# backplane_main.net
KiCad netlist of a schematic drawn in Altium Designer
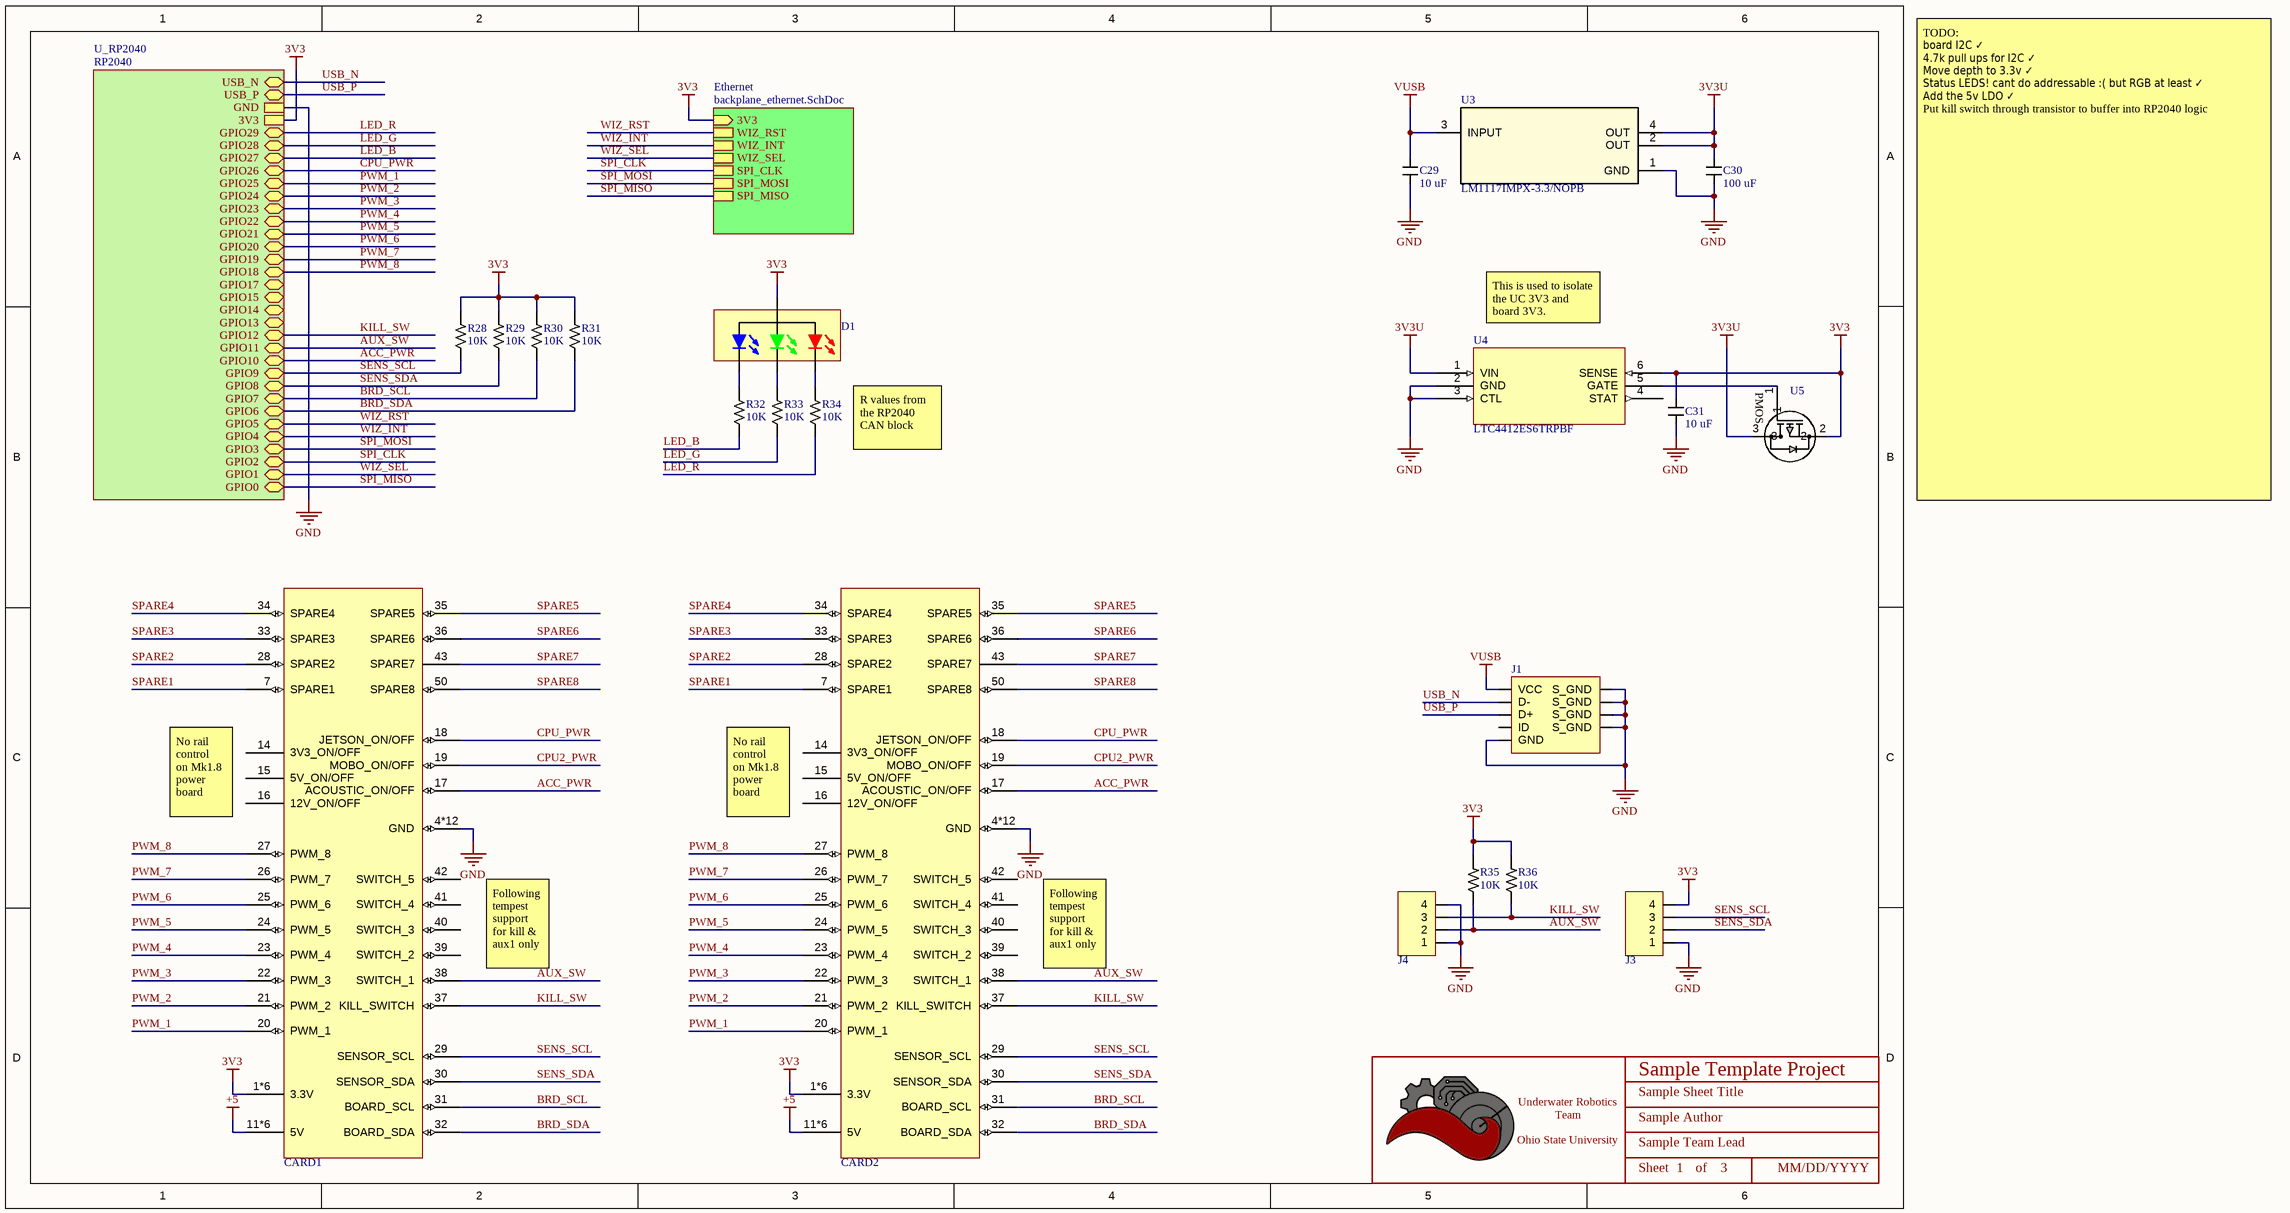
[diagram p0: backplane_main.SchDoc]

(export (version "E")
  (design (tool "Eeschema 10.0.6"))
  (components
    (comp (ref "*")
      (value "Title_Block")
      (footprint "LOGO")
      (description "UWRT Schematic Title Block Template\r\n\r\nCreated June 2021, Dylan Trainor")
      (libsource (lib "UWRT") (part "Title_Block"))
    )
    (comp (ref "C29")
      (value "10uF Ceramic 6.3V")
      (footprint "CAPACITOR_0603")
      (description "Cap 10uF 6.3V +/-20%\r\nCeramic 0603")
      (fields
        (field (name "TOLERANCE") "+/- 20%")
        (field (name "VOLTAGE") "6.3V")
        (field (name "VALUE (UF)") "10 uF")
        (field (name "MADE BY") "Flip B")
      )
      (libsource (lib "Capacitors") (part "CAPACITOR_10uF_0603"))
    )
    (comp (ref "C30")
      (value "100uF Ceramic 6.3V")
      (footprint "CAPACITOR_0603")
      (description "Cap 100uF 6.3V +/-20%\r\nCeramic 0603")
      (fields
        (field (name "TOLERANCE") "+/- 20%")
        (field (name "VOLTAGE") "6.3V")
        (field (name "VALUE (UF)") "100 uF")
        (field (name "MADE BY") "Dylan Trainor")
      )
      (libsource (lib "Capacitors") (part "CAPACITOR_100uF_0603"))
    )
    (comp (ref "C31")
      (value "10uF Ceramic 6.3V")
      (footprint "CAPACITOR_0603")
      (description "Cap 10uF 6.3V +/-20%\r\nCeramic 0603")
      (fields
        (field (name "TOLERANCE") "+/- 20%")
        (field (name "VOLTAGE") "6.3V")
        (field (name "VALUE (UF)") "10 uF")
        (field (name "MADE BY") "Flip B")
      )
      (libsource (lib "Capacitors") (part "CAPACITOR_10uF_0603"))
    )
    (comp (ref "CARD1")
      (value "BACKPLANE_EDGE_SOCKET")
      (footprint "SOCKET_BACKPLANE_EDGE_CONN")
      (description "Backplane Edge Socket")
      (fields (field (name "MADE BY") "Robert Pafford"))
      (libsource (lib "Connectors") (part "BACKPLANE_EDGE_SOCKET"))
    )
    (comp (ref "CARD2")
      (value "BACKPLANE_EDGE_SOCKET")
      (footprint "SOCKET_BACKPLANE_EDGE_CONN")
      (description "Backplane Edge Socket")
      (fields (field (name "MADE BY") "Robert Pafford"))
      (libsource (lib "Connectors") (part "BACKPLANE_EDGE_SOCKET"))
    )
    (comp (ref "D1")
      (value "EAST1616RGBB4")
      (footprint "LED_0606_4SMD")
      (description "LED RGB CLEAR 4SMD")
      (fields (field (name "MADE BY") "Robert Pafford"))
      (libsource (lib "Diodes") (part "LED_RGB_4SMD"))
    )
    (comp (ref "J1")
      (value "USB_MICRO R/A")
      (footprint "CONN_MINIUSB")
      (description "Amphenol Micro USB-B\r\nUSB2.0 5 Pin Right Angle SMD")
      (fields (field (name "MANUFACTURER") "Amphenol") (field (name "CREATED BY") "Flip B"))
      (libsource (lib "Connectors") (part "CONN_MICROUSB"))
    )
    (comp (ref "J3")
      (value "Mini-Fit Jr R/A")
      (footprint "CONN_MOLEX_MINIFIT JR_4 POS_R/A")
      (description "Molex Minifit Jr. 5569 \r\n4 Pos R/A Natural")
      (fields (field (name "MANUFACTURER") "Molex") (field (name "CREATED BY") "Flip B"))
      (libsource (lib "Connectors") (part "CONN_MOLEX_MINIFIT JR_4POS_R/A"))
    )
    (comp (ref "J4")
      (value "Mini-Fit Jr R/A")
      (footprint "CONN_MOLEX_MINIFIT JR_4 POS_R/A")
      (description "Molex Minifit Jr. 5569 \r\n4 Pos R/A Natural")
      (fields (field (name "MANUFACTURER") "Molex") (field (name "CREATED BY") "Flip B"))
      (libsource (lib "Connectors") (part "CONN_MOLEX_MINIFIT JR_4POS_R/A"))
    )
    (comp (ref "R28")
      (value "10k Ohm 5% 1/10W")
      (footprint "RESISTOR_0603")
      (description "RES 10k OHM 5% 1/10W 0603")
      (fields
        (field (name "TOLERANCE") "+/- 5%")
        (field (name "VALUE  (OHMS)") "10K")
        (field (name "MADE BY") "Robert Pafford")
      )
      (libsource (lib "Resistors") (part "RESISTOR_10K_0603"))
    )
    (comp (ref "R29")
      (value "10k Ohm 5% 1/10W")
      (footprint "RESISTOR_0603")
      (description "RES 10k OHM 5% 1/10W 0603")
      (fields
        (field (name "TOLERANCE") "+/- 5%")
        (field (name "VALUE  (OHMS)") "10K")
        (field (name "MADE BY") "Robert Pafford")
      )
      (libsource (lib "Resistors") (part "RESISTOR_10K_0603"))
    )
    (comp (ref "R30")
      (value "10k Ohm 5% 1/10W")
      (footprint "RESISTOR_0603")
      (description "RES 10k OHM 5% 1/10W 0603")
      (fields
        (field (name "TOLERANCE") "+/- 5%")
        (field (name "VALUE  (OHMS)") "10K")
        (field (name "MADE BY") "Robert Pafford")
      )
      (libsource (lib "Resistors") (part "RESISTOR_10K_0603"))
    )
    (comp (ref "R31")
      (value "10k Ohm 5% 1/10W")
      (footprint "RESISTOR_0603")
      (description "RES 10k OHM 5% 1/10W 0603")
      (fields
        (field (name "TOLERANCE") "+/- 5%")
        (field (name "VALUE  (OHMS)") "10K")
        (field (name "MADE BY") "Robert Pafford")
      )
      (libsource (lib "Resistors") (part "RESISTOR_10K_0603"))
    )
    (comp (ref "R32")
      (value "10k Ohm 5% 1/10W")
      (footprint "RESISTOR_0603")
      (description "RES 10k OHM 5% 1/10W 0603")
      (fields
        (field (name "TOLERANCE") "+/- 5%")
        (field (name "VALUE  (OHMS)") "10K")
        (field (name "MADE BY") "Robert Pafford")
      )
      (libsource (lib "Resistors") (part "RESISTOR_10K_0603"))
    )
    (comp (ref "R33")
      (value "10k Ohm 5% 1/10W")
      (footprint "RESISTOR_0603")
      (description "RES 10k OHM 5% 1/10W 0603")
      (fields
        (field (name "TOLERANCE") "+/- 5%")
        (field (name "VALUE  (OHMS)") "10K")
        (field (name "MADE BY") "Robert Pafford")
      )
      (libsource (lib "Resistors") (part "RESISTOR_10K_0603"))
    )
    (comp (ref "R34")
      (value "10k Ohm 5% 1/10W")
      (footprint "RESISTOR_0603")
      (description "RES 10k OHM 5% 1/10W 0603")
      (fields
        (field (name "TOLERANCE") "+/- 5%")
        (field (name "VALUE  (OHMS)") "10K")
        (field (name "MADE BY") "Robert Pafford")
      )
      (libsource (lib "Resistors") (part "RESISTOR_10K_0603"))
    )
    (comp (ref "R35")
      (value "10k Ohm 5% 1/10W")
      (footprint "RESISTOR_0603")
      (description "RES 10k OHM 5% 1/10W 0603")
      (fields
        (field (name "TOLERANCE") "+/- 5%")
        (field (name "VALUE  (OHMS)") "10K")
        (field (name "MADE BY") "Robert Pafford")
      )
      (libsource (lib "Resistors") (part "RESISTOR_10K_0603"))
    )
    (comp (ref "R36")
      (value "10k Ohm 5% 1/10W")
      (footprint "RESISTOR_0603")
      (description "RES 10k OHM 5% 1/10W 0603")
      (fields
        (field (name "TOLERANCE") "+/- 5%")
        (field (name "VALUE  (OHMS)") "10K")
        (field (name "MADE BY") "Robert Pafford")
      )
      (libsource (lib "Resistors") (part "RESISTOR_10K_0603"))
    )
    (comp (ref "U3")
      (value "LM1117IMPX-3.3/NOPB")
      (footprint "SOT-223-4")
      (description "IC REG LIN 3.3V 800MA SOT223-4")
      (fields
        (field (name "PARTNUMBER") "LM1117IMP-3.3/NOPB")
        (field (name "MANUFACTURER") "Texas Instruments")
        (field (name "CREATED BY") "Dylan T")
      )
      (libsource (lib "Converter") (part "LM1117IMPX-3.3/NOPB"))
    )
    (comp (ref "U4")
      (value "LTC4412ES6TRPBF")
      (footprint "TSOT-23_S6")
      (description "OR Controller Source Selector Switch P-Channel 2:1 TSOT-23-6")
      (fields (field (name "MP") "LTC4412ES6#TRPBF") (field (name "MF") "Analog Devices"))
      (libsource (lib "Integrated Circuits") (part "LTC4412ES6TRPBF"))
    )
    (comp (ref "U5")
      (value "MOSFET P-CHANNEL 20V 4.7A SOT23")
      (footprint "SOT-23-3")
      (description "P-Channel 20 V 4.7A (Tc) 1.56W (Tc) Surface Mount SOT-23")
      (fields
        (field (name "MANUFACTURER_PART_NUMBER") "TSM500P02CX")
        (field (name "CREATED BY") "Robert Pafford")
      )
      (libsource (lib "Transistors") (part "TSM500P02CX"))
    )
  )
  (nets
    (net (code "1") (name "+5") (class "Default")
      (node (ref "CARD1") (pin "11*6") (pinfunction "5V_11*6") (pintype "power_in"))
      (node (ref "CARD2") (pin "11*6") (pinfunction "5V_11*6") (pintype "power_in"))
    )
    (net (code "2") (name "/ACC_PWR") (class "Default")
      (node (ref "CARD1") (pin "17") (pinfunction "ACOUSTIC_ON/OFF_17") (pintype "bidirectional"))
      (node (ref "CARD2") (pin "17") (pinfunction "ACOUSTIC_ON/OFF_17") (pintype "bidirectional"))
    )
    (net (code "3") (name "/AUX_SW") (class "Default")
      (node (ref "CARD1") (pin "38") (pinfunction "SWITCH_1_38") (pintype "bidirectional"))
      (node (ref "CARD2") (pin "38") (pinfunction "SWITCH_1_38") (pintype "bidirectional"))
      (node (ref "J4") (pin "2") (pinfunction "2_2") (pintype "passive"))
      (node (ref "R35") (pin "2") (pinfunction "2_2") (pintype "passive"))
    )
    (net (code "4") (name "/BRD_SCL") (class "Default")
      (node (ref "CARD1") (pin "31") (pinfunction "BOARD_SCL_31") (pintype "bidirectional"))
      (node (ref "CARD2") (pin "31") (pinfunction "BOARD_SCL_31") (pintype "bidirectional"))
      (node (ref "R30") (pin "2") (pinfunction "2_2") (pintype "passive"))
    )
    (net (code "5") (name "/BRD_SDA") (class "Default")
      (node (ref "CARD1") (pin "32") (pinfunction "BOARD_SDA_32") (pintype "bidirectional"))
      (node (ref "CARD2") (pin "32") (pinfunction "BOARD_SDA_32") (pintype "bidirectional"))
      (node (ref "R31") (pin "2") (pinfunction "2_2") (pintype "passive"))
    )
    (net (code "6") (name "/CPU2_PWR") (class "Default")
      (node (ref "CARD1") (pin "19") (pinfunction "MOBO_ON/OFF_19") (pintype "bidirectional"))
      (node (ref "CARD2") (pin "19") (pinfunction "MOBO_ON/OFF_19") (pintype "bidirectional"))
    )
    (net (code "7") (name "/CPU_PWR") (class "Default")
      (node (ref "CARD1") (pin "18") (pinfunction "JETSON_ON/OFF_18") (pintype "bidirectional"))
      (node (ref "CARD2") (pin "18") (pinfunction "JETSON_ON/OFF_18") (pintype "bidirectional"))
    )
    (net (code "12") (name "/KILL_SW") (class "Default")
      (node (ref "CARD1") (pin "37") (pinfunction "KILL_SWITCH_37") (pintype "bidirectional"))
      (node (ref "CARD2") (pin "37") (pinfunction "KILL_SWITCH_37") (pintype "bidirectional"))
      (node (ref "J4") (pin "3") (pinfunction "3_3") (pintype "passive"))
      (node (ref "R36") (pin "2") (pinfunction "2_2") (pintype "passive"))
    )
    (net (code "13") (name "/LED_B") (class "Default")
      (node (ref "R32") (pin "2") (pinfunction "2_2") (pintype "passive"))
    )
    (net (code "14") (name "/LED_G") (class "Default")
      (node (ref "R33") (pin "2") (pinfunction "2_2") (pintype "passive"))
    )
    (net (code "15") (name "/LED_R") (class "Default")
      (node (ref "R34") (pin "2") (pinfunction "2_2") (pintype "passive"))
    )
    (net (code "16") (name "/PWM_1") (class "Default")
      (node (ref "CARD1") (pin "20") (pinfunction "PWM_1_20") (pintype "bidirectional"))
      (node (ref "CARD2") (pin "20") (pinfunction "PWM_1_20") (pintype "bidirectional"))
    )
    (net (code "17") (name "/PWM_2") (class "Default")
      (node (ref "CARD1") (pin "21") (pinfunction "PWM_2_21") (pintype "bidirectional"))
      (node (ref "CARD2") (pin "21") (pinfunction "PWM_2_21") (pintype "bidirectional"))
    )
    (net (code "18") (name "/PWM_3") (class "Default")
      (node (ref "CARD1") (pin "22") (pinfunction "PWM_3_22") (pintype "bidirectional"))
      (node (ref "CARD2") (pin "22") (pinfunction "PWM_3_22") (pintype "bidirectional"))
    )
    (net (code "19") (name "/PWM_4") (class "Default")
      (node (ref "CARD1") (pin "23") (pinfunction "PWM_4_23") (pintype "bidirectional"))
      (node (ref "CARD2") (pin "23") (pinfunction "PWM_4_23") (pintype "bidirectional"))
    )
    (net (code "20") (name "/PWM_5") (class "Default")
      (node (ref "CARD1") (pin "24") (pinfunction "PWM_5_24") (pintype "bidirectional"))
      (node (ref "CARD2") (pin "24") (pinfunction "PWM_5_24") (pintype "bidirectional"))
    )
    (net (code "21") (name "/PWM_6") (class "Default")
      (node (ref "CARD1") (pin "25") (pinfunction "PWM_6_25") (pintype "bidirectional"))
      (node (ref "CARD2") (pin "25") (pinfunction "PWM_6_25") (pintype "bidirectional"))
    )
    (net (code "22") (name "/PWM_7") (class "Default")
      (node (ref "CARD1") (pin "26") (pinfunction "PWM_7_26") (pintype "bidirectional"))
      (node (ref "CARD2") (pin "26") (pinfunction "PWM_7_26") (pintype "bidirectional"))
    )
    (net (code "23") (name "/PWM_8") (class "Default")
      (node (ref "CARD1") (pin "27") (pinfunction "PWM_8_27") (pintype "bidirectional"))
      (node (ref "CARD2") (pin "27") (pinfunction "PWM_8_27") (pintype "bidirectional"))
    )
    (net (code "24") (name "/SENS_SCL") (class "Default")
      (node (ref "CARD1") (pin "29") (pinfunction "SENSOR_SCL_29") (pintype "bidirectional"))
      (node (ref "CARD2") (pin "29") (pinfunction "SENSOR_SCL_29") (pintype "bidirectional"))
      (node (ref "J3") (pin "3") (pinfunction "3_3") (pintype "passive"))
      (node (ref "R28") (pin "2") (pinfunction "2_2") (pintype "passive"))
    )
    (net (code "25") (name "/SENS_SDA") (class "Default")
      (node (ref "CARD1") (pin "30") (pinfunction "SENSOR_SDA_30") (pintype "bidirectional"))
      (node (ref "CARD2") (pin "30") (pinfunction "SENSOR_SDA_30") (pintype "bidirectional"))
      (node (ref "J3") (pin "2") (pinfunction "2_2") (pintype "passive"))
      (node (ref "R29") (pin "2") (pinfunction "2_2") (pintype "passive"))
    )
    (net (code "26") (name "/SPARE1") (class "Default")
      (node (ref "CARD1") (pin "7") (pinfunction "SPARE1_7") (pintype "bidirectional"))
      (node (ref "CARD2") (pin "7") (pinfunction "SPARE1_7") (pintype "bidirectional"))
    )
    (net (code "27") (name "/SPARE2") (class "Default")
      (node (ref "CARD1") (pin "28") (pinfunction "SPARE2_28") (pintype "bidirectional"))
      (node (ref "CARD2") (pin "28") (pinfunction "SPARE2_28") (pintype "bidirectional"))
    )
    (net (code "28") (name "/SPARE3") (class "Default")
      (node (ref "CARD1") (pin "33") (pinfunction "SPARE3_33") (pintype "bidirectional"))
      (node (ref "CARD2") (pin "33") (pinfunction "SPARE3_33") (pintype "bidirectional"))
    )
    (net (code "29") (name "/SPARE4") (class "Default")
      (node (ref "CARD1") (pin "34") (pinfunction "SPARE4_34") (pintype "bidirectional"))
      (node (ref "CARD2") (pin "34") (pinfunction "SPARE4_34") (pintype "bidirectional"))
    )
    (net (code "30") (name "/SPARE5") (class "Default")
      (node (ref "CARD1") (pin "35") (pinfunction "SPARE5_35") (pintype "bidirectional"))
      (node (ref "CARD2") (pin "35") (pinfunction "SPARE5_35") (pintype "bidirectional"))
    )
    (net (code "31") (name "/SPARE6") (class "Default")
      (node (ref "CARD1") (pin "36") (pinfunction "SPARE6_36") (pintype "bidirectional"))
      (node (ref "CARD2") (pin "36") (pinfunction "SPARE6_36") (pintype "bidirectional"))
    )
    (net (code "32") (name "/SPARE7") (class "Default")
      (node (ref "CARD1") (pin "43") (pinfunction "SPARE7_43") (pintype "power_in"))
      (node (ref "CARD2") (pin "43") (pinfunction "SPARE7_43") (pintype "power_in"))
    )
    (net (code "33") (name "/SPARE8") (class "Default")
      (node (ref "CARD1") (pin "50") (pinfunction "SPARE8_50") (pintype "bidirectional"))
      (node (ref "CARD2") (pin "50") (pinfunction "SPARE8_50") (pintype "bidirectional"))
    )
    (net (code "37") (name "/USB_N") (class "Default")
      (node (ref "J1") (pin "2") (pinfunction "D-_2") (pintype "passive"))
    )
    (net (code "38") (name "/USB_P") (class "Default")
      (node (ref "J1") (pin "3") (pinfunction "D+_3") (pintype "passive"))
    )
    (net (code "42") (name "3V3") (class "Default")
      (node (ref "C31") (pin "1") (pinfunction "1_1") (pintype "passive"))
      (node (ref "CARD1") (pin "1*6") (pinfunction "3.3V_1*6") (pintype "power_in"))
      (node (ref "CARD2") (pin "1*6") (pinfunction "3.3V_1*6") (pintype "power_in"))
      (node (ref "D1") (pin "4") (pinfunction "4_4") (pintype "passive"))
      (node (ref "J3") (pin "4") (pinfunction "4_4") (pintype "passive"))
      (node (ref "R28") (pin "1") (pinfunction "1_1") (pintype "passive"))
      (node (ref "R29") (pin "1") (pinfunction "1_1") (pintype "passive"))
      (node (ref "R30") (pin "1") (pinfunction "1_1") (pintype "passive"))
      (node (ref "R31") (pin "1") (pinfunction "1_1") (pintype "passive"))
      (node (ref "R35") (pin "1") (pinfunction "1_1") (pintype "passive"))
      (node (ref "R36") (pin "1") (pinfunction "1_1") (pintype "passive"))
      (node (ref "U4") (pin "6") (pinfunction "SENSE_6") (pintype "input"))
      (node (ref "U5") (pin "2") (pinfunction "2_2") (pintype "passive"))
    )
    (net (code "43") (name "3V3U") (class "Default")
      (node (ref "C30") (pin "1") (pinfunction "1_1") (pintype "passive"))
      (node (ref "U3") (pin "2") (pinfunction "OUT_2") (pintype "power_in"))
      (node (ref "U3") (pin "4") (pinfunction "OUT_4") (pintype "power_in"))
      (node (ref "U4") (pin "1") (pinfunction "VIN_1") (pintype "input"))
      (node (ref "U5") (pin "3") (pinfunction "3_3") (pintype "passive"))
    )
    (net (code "44") (name "GND") (class "Default")
      (node (ref "C29") (pin "2") (pinfunction "2_2") (pintype "passive"))
      (node (ref "C30") (pin "2") (pinfunction "2_2") (pintype "passive"))
      (node (ref "C31") (pin "2") (pinfunction "2_2") (pintype "passive"))
      (node (ref "CARD1") (pin "4*12") (pinfunction "GND_4*12") (pintype "bidirectional"))
      (node (ref "CARD2") (pin "4*12") (pinfunction "GND_4*12") (pintype "bidirectional"))
      (node (ref "J1") (pin "5") (pinfunction "GND_5") (pintype "passive"))
      (node (ref "J1") (pin "6") (pinfunction "S_GND_6") (pintype "passive"))
      (node (ref "J1") (pin "7") (pinfunction "S_GND_7") (pintype "passive"))
      (node (ref "J1") (pin "8") (pinfunction "S_GND_8") (pintype "passive"))
      (node (ref "J1") (pin "9") (pinfunction "S_GND_9") (pintype "passive"))
      (node (ref "J3") (pin "1") (pinfunction "1_1") (pintype "passive"))
      (node (ref "J4") (pin "1") (pinfunction "1_1") (pintype "passive"))
      (node (ref "J4") (pin "4") (pinfunction "4_4") (pintype "passive"))
      (node (ref "U3") (pin "1") (pinfunction "GND_1") (pintype "power_in"))
      (node (ref "U4") (pin "2") (pinfunction "GND_2") (pintype "power_in"))
      (node (ref "U4") (pin "3") (pinfunction "CTL_3") (pintype "input"))
    )
    (net (code "45") (name "Net-(D1-32)") (class "Default")
      (node (ref "D1") (pin "3") (pinfunction "32_3") (pintype "passive"))
      (node (ref "R32") (pin "1") (pinfunction "1_1") (pintype "passive"))
    )
    (net (code "46") (name "Net-(D1-Pad1)") (class "Default")
      (node (ref "D1") (pin "1") (pinfunction "1_1") (pintype "passive"))
      (node (ref "R34") (pin "1") (pinfunction "1_1") (pintype "passive"))
    )
    (net (code "47") (name "Net-(D1-Pad2)") (class "Default")
      (node (ref "D1") (pin "2") (pinfunction "2_2") (pintype "passive"))
      (node (ref "R33") (pin "1") (pinfunction "1_1") (pintype "passive"))
    )
    (net (code "48") (name "Net-(U4-GATE)") (class "Default")
      (node (ref "U4") (pin "5") (pinfunction "GATE_5") (pintype "passive"))
      (node (ref "U5") (pin "1") (pinfunction "1_1") (pintype "passive"))
    )
    (net (code "49") (name "VUSB") (class "Default")
      (node (ref "C29") (pin "1") (pinfunction "1_1") (pintype "passive"))
      (node (ref "J1") (pin "1") (pinfunction "VCC_1") (pintype "passive"))
      (node (ref "U3") (pin "3") (pinfunction "INPUT_3") (pintype "power_in"))
    )
    (net (code "50") (name "unconnected-(CARD1-3V3_ON{slash}OFF-Pad14)") (class "Default")
      (node (ref "CARD1") (pin "14") (pinfunction "3V3_ON/OFF_14") (pintype "power_in"))
    )
    (net (code "51") (name "unconnected-(CARD1-5V_ON{slash}OFF-Pad15)") (class "Default")
      (node (ref "CARD1") (pin "15") (pinfunction "5V_ON/OFF_15") (pintype "power_in"))
    )
    (net (code "52") (name "unconnected-(CARD1-12V_ON{slash}OFF-Pad16)") (class "Default")
      (node (ref "CARD1") (pin "16") (pinfunction "12V_ON/OFF_16") (pintype "power_in"))
    )
    (net (code "53") (name "unconnected-(CARD1-SWITCH_2-Pad39)") (class "Default")
      (node (ref "CARD1") (pin "39") (pinfunction "SWITCH_2_39") (pintype "bidirectional"))
    )
    (net (code "54") (name "unconnected-(CARD1-SWITCH_3-Pad40)") (class "Default")
      (node (ref "CARD1") (pin "40") (pinfunction "SWITCH_3_40") (pintype "bidirectional"))
    )
    (net (code "55") (name "unconnected-(CARD1-SWITCH_4-Pad41)") (class "Default")
      (node (ref "CARD1") (pin "41") (pinfunction "SWITCH_4_41") (pintype "bidirectional"))
    )
    (net (code "56") (name "unconnected-(CARD1-SWITCH_5-Pad42)") (class "Default")
      (node (ref "CARD1") (pin "42") (pinfunction "SWITCH_5_42") (pintype "bidirectional"))
    )
    (net (code "57") (name "unconnected-(CARD2-3V3_ON{slash}OFF-Pad14)") (class "Default")
      (node (ref "CARD2") (pin "14") (pinfunction "3V3_ON/OFF_14") (pintype "power_in"))
    )
    (net (code "58") (name "unconnected-(CARD2-5V_ON{slash}OFF-Pad15)") (class "Default")
      (node (ref "CARD2") (pin "15") (pinfunction "5V_ON/OFF_15") (pintype "power_in"))
    )
    (net (code "59") (name "unconnected-(CARD2-12V_ON{slash}OFF-Pad16)") (class "Default")
      (node (ref "CARD2") (pin "16") (pinfunction "12V_ON/OFF_16") (pintype "power_in"))
    )
    (net (code "60") (name "unconnected-(CARD2-SWITCH_2-Pad39)") (class "Default")
      (node (ref "CARD2") (pin "39") (pinfunction "SWITCH_2_39") (pintype "bidirectional"))
    )
    (net (code "61") (name "unconnected-(CARD2-SWITCH_3-Pad40)") (class "Default")
      (node (ref "CARD2") (pin "40") (pinfunction "SWITCH_3_40") (pintype "bidirectional"))
    )
    (net (code "62") (name "unconnected-(CARD2-SWITCH_4-Pad41)") (class "Default")
      (node (ref "CARD2") (pin "41") (pinfunction "SWITCH_4_41") (pintype "bidirectional"))
    )
    (net (code "63") (name "unconnected-(CARD2-SWITCH_5-Pad42)") (class "Default")
      (node (ref "CARD2") (pin "42") (pinfunction "SWITCH_5_42") (pintype "bidirectional"))
    )
    (net (code "64") (name "unconnected-(J1-ID-Pad4)") (class "Default")
      (node (ref "J1") (pin "4") (pinfunction "ID_4") (pintype "passive"))
    )
    (net (code "65") (name "unconnected-(U4-STAT-Pad4)") (class "Default")
      (node (ref "U4") (pin "4") (pinfunction "STAT_4") (pintype "output"))
    )
  )
)
